# mini.net
KiCad netlist of a schematic drawn in Altium Designer
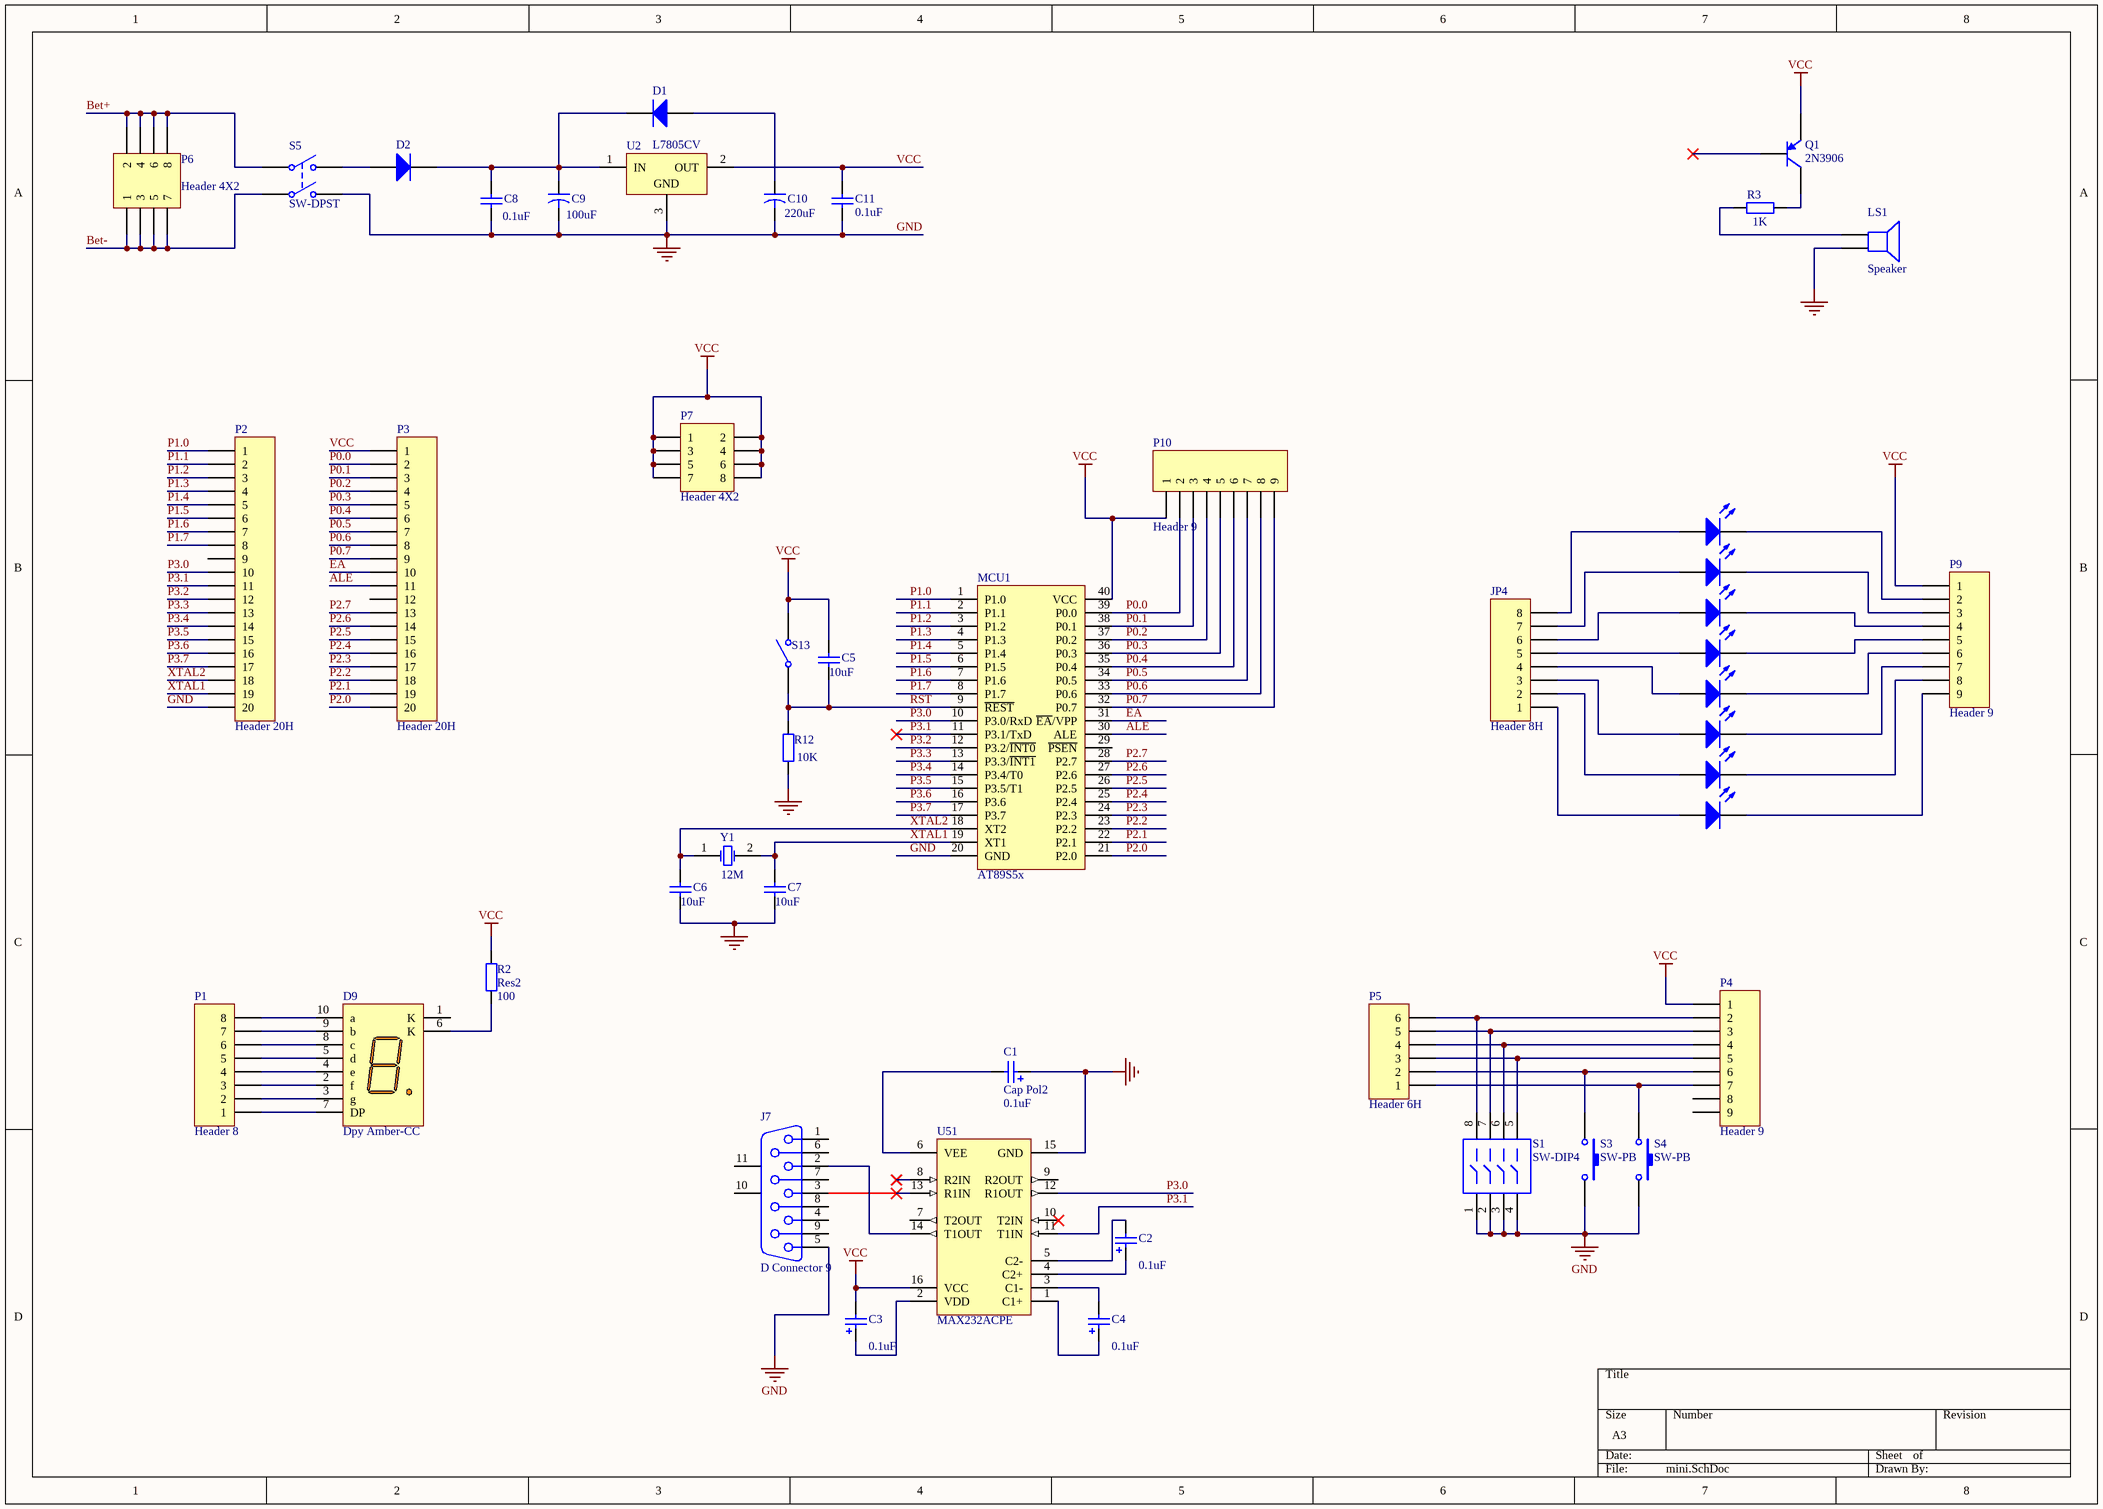
[diagram p0: mini.SchDoc]

(export (version "E")
  (design (tool "Eeschema 10.0.6"))
  (components
    (comp (ref "C1")
      (value "Cap Pol2")
      (footprint "POLAR0.8")
      (description "Polarized Capacitor (Axial)")
      (fields (field (name "ALTIUM_VALUE") "0.1uF") (field (name "PUBLISHER") "Altium Limited"))
      (libsource (lib "Miscellaneous Devices") (part "Cap Pol2"))
    )
    (comp (ref "C2")
      (value "0.1uF")
      (footprint "POLAR0.8")
      (description "Polarized Capacitor (Axial)")
      (fields (field (name "Comment") "Cap Pol2") (field (name "PUBLISHER") "Altium Limited"))
      (libsource (lib "Miscellaneous Devices") (part "Cap Pol2"))
    )
    (comp (ref "C3")
      (value "0.1uF")
      (footprint "POLAR0.8")
      (description "Polarized Capacitor (Axial)")
      (fields (field (name "Comment") "Cap Pol2") (field (name "PUBLISHER") "Altium Limited"))
      (libsource (lib "Miscellaneous Devices") (part "Cap Pol2"))
    )
    (comp (ref "C4")
      (value "0.1uF")
      (footprint "POLAR0.8")
      (description "Polarized Capacitor (Axial)")
      (fields (field (name "Comment") "Cap Pol2") (field (name "PUBLISHER") "Altium Limited"))
      (libsource (lib "Miscellaneous Devices") (part "Cap Pol2"))
    )
    (comp (ref "C5")
      (value "10uF")
      (footprint "CC 2.2*5")
      (description "Capacitor")
      (fields (field (name "Comment") "Cap") (field (name "PUBLISHER") "Altium Limited"))
      (libsource (lib "Miscellaneous Devices") (part "Cap"))
    )
    (comp (ref "C6")
      (value "10uF")
      (footprint "RAD-0.3")
      (description "Capacitor")
      (fields (field (name "Comment") "Cap") (field (name "PUBLISHER") "Altium Limited"))
      (libsource (lib "Miscellaneous Devices") (part "Cap"))
    )
    (comp (ref "C7")
      (value "10uF")
      (footprint "RAD-0.3")
      (description "Capacitor")
      (fields (field (name "Comment") "Cap") (field (name "PUBLISHER") "Altium Limited"))
      (libsource (lib "Miscellaneous Devices") (part "Cap"))
    )
    (comp (ref "C8")
      (value "0.1uF")
      (footprint "RAD-0.3")
      (description "Capacitor")
      (fields (field (name "Comment") "Cap") (field (name "PUBLISHER") "Altium Limited"))
      (libsource (lib "Miscellaneous Devices") (part "Cap"))
    )
    (comp (ref "C9")
      (value "100uF")
      (footprint "CAPR5-4X5")
      (description "Capacitor")
      (fields (field (name "Comment") "Cap2") (field (name "PUBLISHER") "Altium Limited"))
      (libsource (lib "Miscellaneous Devices") (part "Cap2"))
    )
    (comp (ref "C10")
      (value "220uF")
      (footprint "CAPR5-4X5")
      (description "Capacitor")
      (fields (field (name "Comment") "Cap2") (field (name "PUBLISHER") "Altium Limited"))
      (libsource (lib "Miscellaneous Devices") (part "Cap2"))
    )
    (comp (ref "C11")
      (value "0.1uF")
      (footprint "RAD-0.3")
      (description "Capacitor")
      (fields (field (name "Comment") "Cap") (field (name "PUBLISHER") "Altium Limited"))
      (libsource (lib "Miscellaneous Devices") (part "Cap"))
    )
    (comp (ref "D1")
      (value "Diode 1N4007")
      (footprint "DIODE-0.4")
      (description "1 Amp General Purpose Rectifier")
      (fields (field (name "PUBLISHER") "Altium Limited"))
      (libsource (lib "Miscellaneous Devices") (part "Diode 1N4007"))
    )
    (comp (ref "D2")
      (value "Diode 1N4148")
      (footprint "DIODE-0.4")
      (description "High Conductance Fast Diode")
      (fields (field (name "PUBLISHER") "Altium Limited"))
      (libsource (lib "Miscellaneous Devices") (part "Diode 1N4148"))
    )
    (comp (ref "D9")
      (value "Dpy Amber-CC")
      (footprint "H")
      (description "7.6 mm Black Surface 7-Segment Display: CC, RH DP")
      (fields (field (name "PUBLISHER") "Altium Limited"))
      (libsource (lib "Miscellaneous Devices") (part "Dpy Amber-CC"))
    )
    (comp (ref "DS11")
      (value "LED0")
      (footprint "PIN2")
      (description "Typical INFRARED GaAs LED")
      (fields (field (name "PUBLISHER") "Altium Limited"))
      (libsource (lib "Miscellaneous Devices") (part "LED0"))
    )
    (comp (ref "DS12")
      (value "LED0")
      (footprint "PIN2")
      (description "Typical INFRARED GaAs LED")
      (fields (field (name "PUBLISHER") "Altium Limited"))
      (libsource (lib "Miscellaneous Devices") (part "LED0"))
    )
    (comp (ref "DS13")
      (value "LED0")
      (footprint "PIN2")
      (description "Typical INFRARED GaAs LED")
      (fields (field (name "PUBLISHER") "Altium Limited"))
      (libsource (lib "Miscellaneous Devices") (part "LED0"))
    )
    (comp (ref "DS14")
      (value "LED0")
      (footprint "PIN2")
      (description "Typical INFRARED GaAs LED")
      (fields (field (name "PUBLISHER") "Altium Limited"))
      (libsource (lib "Miscellaneous Devices") (part "LED0"))
    )
    (comp (ref "DS15")
      (value "LED0")
      (footprint "PIN2")
      (description "Typical INFRARED GaAs LED")
      (fields (field (name "PUBLISHER") "Altium Limited"))
      (libsource (lib "Miscellaneous Devices") (part "LED0"))
    )
    (comp (ref "DS16")
      (value "LED0")
      (footprint "PIN2")
      (description "Typical INFRARED GaAs LED")
      (fields (field (name "PUBLISHER") "Altium Limited"))
      (libsource (lib "Miscellaneous Devices") (part "LED0"))
    )
    (comp (ref "DS17")
      (value "LED0")
      (footprint "PIN2")
      (description "Typical INFRARED GaAs LED")
      (fields (field (name "PUBLISHER") "Altium Limited"))
      (libsource (lib "Miscellaneous Devices") (part "LED0"))
    )
    (comp (ref "DS18")
      (value "LED0")
      (footprint "PIN2")
      (description "Typical INFRARED GaAs LED")
      (fields (field (name "PUBLISHER") "Altium Limited"))
      (libsource (lib "Miscellaneous Devices") (part "LED0"))
    )
    (comp (ref "J7")
      (value "D Connector 9")
      (footprint "DSUB1.385-2H9")
      (description "Receptacle Assembly, 9 Position, Right Angle")
      (fields (field (name "PUBLISHER") "Altium Limited"))
      (libsource (lib "Miscellaneous Connectors") (part "D Connector 9"))
    )
    (comp (ref "JP4")
      (value "Header 8H")
      (footprint "HDR1X8H")
      (description "Header, 8-Pin, Right Angle")
      (fields (field (name "PUBLISHER") "Altium Limited"))
      (libsource (lib "Miscellaneous Connectors") (part "Header 8H"))
    )
    (comp (ref "LS1")
      (value "Speaker")
      (footprint "BEEP 7.6X12X7.5")
      (description "Loudspeaker")
      (fields (field (name "PUBLISHER") "Altium Limited"))
      (libsource (lib "Miscellaneous Devices") (part "Speaker"))
    )
    (comp (ref "MCU1")
      (value "AT89S5x")
      (footprint "DIP40")
      (description "51单片机")
      (libsource (lib "单片机") (part "AT89S5x"))
    )
    (comp (ref "P1")
      (value "Header 8")
      (footprint "HDR1X8")
      (description "Header, 8-Pin")
      (fields (field (name "PUBLISHER") "Altium Limited"))
      (libsource (lib "Miscellaneous Connectors") (part "Header 8"))
    )
    (comp (ref "P2")
      (value "Header 20H")
      (footprint "HDR1X20")
      (description "Header, 20-Pin, Right Angle")
      (fields (field (name "PUBLISHER") "Altium Limited"))
      (libsource (lib "Miscellaneous Connectors") (part "Header 20H"))
    )
    (comp (ref "P3")
      (value "Header 20H")
      (footprint "HDR1X20")
      (description "Header, 20-Pin, Right Angle")
      (fields (field (name "PUBLISHER") "Altium Limited"))
      (libsource (lib "Miscellaneous Connectors") (part "Header 20H"))
    )
    (comp (ref "P4")
      (value "Header 9")
      (footprint "HDR1X9")
      (description "Header, 9-Pin")
      (fields (field (name "PUBLISHER") "Altium Limited"))
      (libsource (lib "Miscellaneous Connectors") (part "Header 9"))
    )
    (comp (ref "P5")
      (value "Header 6H")
      (footprint "HDR1X6H")
      (description "Header, 6-Pin, Right Angle")
      (fields (field (name "PUBLISHER") "Altium Limited"))
      (libsource (lib "Miscellaneous Connectors") (part "Header 6H"))
    )
    (comp (ref "P6")
      (value "Header 4X2")
      (footprint "HDR2X4")
      (description "Header, 4-Pin, Dual row")
      (fields (field (name "PUBLISHER") "Altium Limited"))
      (libsource (lib "Miscellaneous Connectors") (part "Header 4X2"))
    )
    (comp (ref "P7")
      (value "Header 4X2")
      (footprint "HDR2X4")
      (description "Header, 4-Pin, Dual row")
      (fields (field (name "PUBLISHER") "Altium Limited"))
      (libsource (lib "PCB_Project") (part "Header 4X2"))
    )
    (comp (ref "P9")
      (value "Header 9")
      (footprint "HDR1X9")
      (description "Header, 9-Pin")
      (fields (field (name "PUBLISHER") "Altium Limited"))
      (libsource (lib "PCB_Project") (part "Header 9"))
    )
    (comp (ref "P10")
      (value "Header 9")
      (footprint "HDR1X9")
      (description "Header, 9-Pin")
      (fields (field (name "PUBLISHER") "Altium Limited"))
      (libsource (lib "") (part "Header 9_1"))
    )
    (comp (ref "Q1")
      (value "2N3906")
      (footprint "BCY-W3/E4")
      (description "PNP General Purpose Amplifier")
      (fields (field (name "PUBLISHER") "Altium Limited"))
      (libsource (lib "Miscellaneous Devices") (part "2N3906"))
    )
    (comp (ref "R2")
      (value "Res2")
      (footprint "AXIAL-0.4")
      (description "Resistor")
      (fields (field (name "ALTIUM_VALUE") "100") (field (name "PUBLISHER") "Altium Limited"))
      (libsource (lib "") (part "Res2_1"))
    )
    (comp (ref "R3")
      (value "1K")
      (footprint "AXIAL-0.4")
      (description "Resistor")
      (fields (field (name "Comment") "Res2") (field (name "PUBLISHER") "Altium Limited"))
      (libsource (lib "Miscellaneous Devices") (part "Res2"))
    )
    (comp (ref "R12")
      (value "10K")
      (footprint "AXIAL-0.4")
      (description "Resistor")
      (fields (field (name "Comment") "Res2") (field (name "PUBLISHER") "Altium Limited"))
      (libsource (lib "") (part "Res2_2"))
    )
    (comp (ref "S1")
      (value "SW-DIP4")
      (footprint "Miscellaneous Devices:DIP-8")
      (description "DIP Switch")
      (fields (field (name "PUBLISHER") "Altium Limited"))
      (libsource (lib "Miscellaneous Devices") (part "SW-DIP4"))
    )
    (comp (ref "S3")
      (value "SW-PB")
      (footprint "SPST-2")
      (description "Switch")
      (fields (field (name "PUBLISHER") "Altium Limited"))
      (libsource (lib "Miscellaneous Devices") (part "SW-PB"))
    )
    (comp (ref "S4")
      (value "SW-PB")
      (footprint "SPST-2")
      (description "Switch")
      (fields (field (name "PUBLISHER") "Altium Limited"))
      (libsource (lib "Miscellaneous Devices") (part "SW-PB"))
    )
    (comp (ref "S5")
      (value "SW-DPST")
      (footprint "DPST-4")
      (description "Double-Pole, Single-Throw Switch")
      (fields (field (name "PUBLISHER") "Altium Limited"))
      (libsource (lib "Miscellaneous Devices") (part "SW-DPST"))
    )
    (comp (ref "S13")
      (value "SW-SPST")
      (footprint "SPST-2")
      (description "Single-Pole, Single-Throw Switch")
      (fields (field (name "PUBLISHER") "Altium Limited"))
      (libsource (lib "Miscellaneous Devices") (part "SW-SPST"))
    )
    (comp (ref "U2")
      (value "L7805CV")
      (footprint "D2PAK_N")
      (description "Positive Voltage Regulator")
      (fields (field (name "PUBLISHER") "Altium Limited"))
      (libsource (lib "ST Power Mgt Voltage Regulator") (part "L7805CV"))
    )
    (comp (ref "U51")
      (value "MAX232ACPE")
      (footprint "DIP-16")
      (description "+5V Powered, Multi-Channel RS-232 Driver/Receiver")
      (fields (field (name "PUBLISHER") "Altium Limited"))
      (libsource (lib "Maxim Communication Transceiver") (part "MAX232ACPE"))
    )
    (comp (ref "Y1")
      (value "12M")
      (footprint "BEEP 7.6X12X7.5")
      (description "Crystal Oscillator")
      (fields (field (name "Comment") "XTAL") (field (name "PUBLISHER") "Altium Limited"))
      (libsource (lib "Miscellaneous Devices") (part "XTAL"))
    )
  )
  (nets
    (net (code "2") (name "/ALE") (class "Default")
      (node (ref "MCU1") (pin "30") (pinfunction "ALE_30") (pintype "passive"))
      (node (ref "P3") (pin "11") (pinfunction "11_11") (pintype "passive"))
    )
    (net (code "3") (name "/Bet+") (class "Default")
      (node (ref "P6") (pin "2") (pinfunction "2_2") (pintype "passive"))
      (node (ref "P6") (pin "4") (pinfunction "4_4") (pintype "passive"))
      (node (ref "P6") (pin "6") (pinfunction "6_6") (pintype "passive"))
      (node (ref "P6") (pin "8") (pinfunction "8_8") (pintype "passive"))
      (node (ref "S5") (pin "1") (pinfunction "COMMON1_1") (pintype "passive"))
    )
    (net (code "4") (name "/Bet-") (class "Default")
      (node (ref "P6") (pin "1") (pinfunction "1_1") (pintype "passive"))
      (node (ref "P6") (pin "3") (pinfunction "3_3") (pintype "passive"))
      (node (ref "P6") (pin "5") (pinfunction "5_5") (pintype "passive"))
      (node (ref "P6") (pin "7") (pinfunction "7_7") (pintype "passive"))
      (node (ref "S5") (pin "3") (pinfunction "COMMON2_3") (pintype "passive"))
    )
    (net (code "5") (name "/P0.0") (class "Default")
      (node (ref "MCU1") (pin "39") (pinfunction "P0.0_39") (pintype "passive"))
      (node (ref "P10") (pin "2") (pinfunction "2_2") (pintype "passive"))
      (node (ref "P3") (pin "2") (pinfunction "2_2") (pintype "passive"))
    )
    (net (code "6") (name "/P0.1") (class "Default")
      (node (ref "MCU1") (pin "38") (pinfunction "P0.1_38") (pintype "passive"))
      (node (ref "P10") (pin "3") (pinfunction "3_3") (pintype "passive"))
      (node (ref "P3") (pin "3") (pinfunction "3_3") (pintype "passive"))
    )
    (net (code "7") (name "/P0.2") (class "Default")
      (node (ref "MCU1") (pin "37") (pinfunction "P0.2_37") (pintype "passive"))
      (node (ref "P10") (pin "4") (pinfunction "4_4") (pintype "passive"))
      (node (ref "P3") (pin "4") (pinfunction "4_4") (pintype "passive"))
    )
    (net (code "8") (name "/P0.3") (class "Default")
      (node (ref "MCU1") (pin "36") (pinfunction "P0.3_36") (pintype "passive"))
      (node (ref "P10") (pin "5") (pinfunction "5_5") (pintype "passive"))
      (node (ref "P3") (pin "5") (pinfunction "5_5") (pintype "passive"))
    )
    (net (code "9") (name "/P0.4") (class "Default")
      (node (ref "MCU1") (pin "35") (pinfunction "P0.4_35") (pintype "passive"))
      (node (ref "P10") (pin "6") (pinfunction "6_6") (pintype "passive"))
      (node (ref "P3") (pin "6") (pinfunction "6_6") (pintype "passive"))
    )
    (net (code "10") (name "/P0.5") (class "Default")
      (node (ref "MCU1") (pin "34") (pinfunction "P0.5_34") (pintype "passive"))
      (node (ref "P10") (pin "7") (pinfunction "7_7") (pintype "passive"))
      (node (ref "P3") (pin "7") (pinfunction "7_7") (pintype "passive"))
    )
    (net (code "11") (name "/P0.6") (class "Default")
      (node (ref "MCU1") (pin "33") (pinfunction "P0.6_33") (pintype "passive"))
      (node (ref "P10") (pin "8") (pinfunction "8_8") (pintype "passive"))
      (node (ref "P3") (pin "8") (pinfunction "8_8") (pintype "passive"))
    )
    (net (code "12") (name "/P0.7") (class "Default")
      (node (ref "MCU1") (pin "32") (pinfunction "P0.7_32") (pintype "passive"))
      (node (ref "P10") (pin "9") (pinfunction "9_9") (pintype "passive"))
      (node (ref "P3") (pin "9") (pinfunction "9_9") (pintype "passive"))
    )
    (net (code "13") (name "/P1.0") (class "Default")
      (node (ref "MCU1") (pin "1") (pinfunction "P1.0_1") (pintype "passive"))
      (node (ref "P2") (pin "1") (pinfunction "1_1") (pintype "passive"))
    )
    (net (code "14") (name "/P1.1") (class "Default")
      (node (ref "MCU1") (pin "2") (pinfunction "P1.1_2") (pintype "passive"))
      (node (ref "P2") (pin "2") (pinfunction "2_2") (pintype "passive"))
    )
    (net (code "15") (name "/P1.2") (class "Default")
      (node (ref "MCU1") (pin "3") (pinfunction "P1.2_3") (pintype "passive"))
      (node (ref "P2") (pin "3") (pinfunction "3_3") (pintype "passive"))
    )
    (net (code "16") (name "/P1.3") (class "Default")
      (node (ref "MCU1") (pin "4") (pinfunction "P1.3_4") (pintype "passive"))
      (node (ref "P2") (pin "4") (pinfunction "4_4") (pintype "passive"))
    )
    (net (code "17") (name "/P1.4") (class "Default")
      (node (ref "MCU1") (pin "5") (pinfunction "P1.4_5") (pintype "passive"))
      (node (ref "P2") (pin "5") (pinfunction "5_5") (pintype "passive"))
    )
    (net (code "18") (name "/P1.5") (class "Default")
      (node (ref "MCU1") (pin "6") (pinfunction "P1.5_6") (pintype "passive"))
      (node (ref "P2") (pin "6") (pinfunction "6_6") (pintype "passive"))
    )
    (net (code "19") (name "/P1.6") (class "Default")
      (node (ref "MCU1") (pin "7") (pinfunction "P1.6_7") (pintype "passive"))
      (node (ref "P2") (pin "7") (pinfunction "7_7") (pintype "passive"))
    )
    (net (code "20") (name "/P1.7") (class "Default")
      (node (ref "MCU1") (pin "8") (pinfunction "P1.7_8") (pintype "passive"))
      (node (ref "P2") (pin "8") (pinfunction "8_8") (pintype "passive"))
    )
    (net (code "21") (name "/P2.0") (class "Default")
      (node (ref "MCU1") (pin "21") (pinfunction "P2.0_21") (pintype "passive"))
      (node (ref "P3") (pin "20") (pinfunction "20_20") (pintype "passive"))
    )
    (net (code "22") (name "/P2.1") (class "Default")
      (node (ref "MCU1") (pin "22") (pinfunction "P2.1_22") (pintype "passive"))
      (node (ref "P3") (pin "19") (pinfunction "19_19") (pintype "passive"))
    )
    (net (code "23") (name "/P2.2") (class "Default")
      (node (ref "MCU1") (pin "23") (pinfunction "P2.2_23") (pintype "passive"))
      (node (ref "P3") (pin "18") (pinfunction "18_18") (pintype "passive"))
    )
    (net (code "24") (name "/P2.3") (class "Default")
      (node (ref "MCU1") (pin "24") (pinfunction "P2.3_24") (pintype "passive"))
      (node (ref "P3") (pin "17") (pinfunction "17_17") (pintype "passive"))
    )
    (net (code "25") (name "/P2.4") (class "Default")
      (node (ref "MCU1") (pin "25") (pinfunction "P2.4_25") (pintype "passive"))
      (node (ref "P3") (pin "16") (pinfunction "16_16") (pintype "passive"))
    )
    (net (code "26") (name "/P2.5") (class "Default")
      (node (ref "MCU1") (pin "26") (pinfunction "P2.5_26") (pintype "passive"))
      (node (ref "P3") (pin "15") (pinfunction "15_15") (pintype "passive"))
    )
    (net (code "27") (name "/P2.6") (class "Default")
      (node (ref "MCU1") (pin "27") (pinfunction "P2.6_27") (pintype "passive"))
      (node (ref "P3") (pin "14") (pinfunction "14_14") (pintype "passive"))
    )
    (net (code "28") (name "/P2.7") (class "Default")
      (node (ref "MCU1") (pin "28") (pinfunction "P2.7_28") (pintype "passive"))
      (node (ref "P3") (pin "13") (pinfunction "13_13") (pintype "passive"))
    )
    (net (code "29") (name "/P3.0") (class "Default")
      (node (ref "MCU1") (pin "10") (pinfunction "P3.0/RxD_10") (pintype "passive"))
      (node (ref "P2") (pin "10") (pinfunction "10_10") (pintype "passive"))
      (node (ref "U51") (pin "12") (pinfunction "R1OUT_12") (pintype "output"))
    )
    (net (code "30") (name "/P3.1") (class "Default")
      (node (ref "MCU1") (pin "11") (pinfunction "P3.1/TxD_11") (pintype "passive"))
      (node (ref "P2") (pin "11") (pinfunction "11_11") (pintype "passive"))
      (node (ref "U51") (pin "11") (pinfunction "T1IN_11") (pintype "input"))
    )
    (net (code "31") (name "/P3.2") (class "Default")
      (node (ref "MCU1") (pin "12") (pinfunction "P3.2/~{INT0}_12") (pintype "passive"))
      (node (ref "P2") (pin "12") (pinfunction "12_12") (pintype "passive"))
    )
    (net (code "32") (name "/P3.3") (class "Default")
      (node (ref "MCU1") (pin "13") (pinfunction "P3.3/~{INT1}_13") (pintype "passive"))
      (node (ref "P2") (pin "13") (pinfunction "13_13") (pintype "passive"))
    )
    (net (code "33") (name "/P3.4") (class "Default")
      (node (ref "MCU1") (pin "14") (pinfunction "P3.4/T0_14") (pintype "passive"))
      (node (ref "P2") (pin "14") (pinfunction "14_14") (pintype "passive"))
    )
    (net (code "34") (name "/P3.5") (class "Default")
      (node (ref "MCU1") (pin "15") (pinfunction "P3.5/T1_15") (pintype "passive"))
      (node (ref "P2") (pin "15") (pinfunction "15_15") (pintype "passive"))
    )
    (net (code "35") (name "/P3.6") (class "Default")
      (node (ref "MCU1") (pin "16") (pinfunction "P3.6_16") (pintype "passive"))
      (node (ref "P2") (pin "16") (pinfunction "16_16") (pintype "passive"))
    )
    (net (code "36") (name "/P3.7") (class "Default")
      (node (ref "MCU1") (pin "17") (pinfunction "P3.7_17") (pintype "passive"))
      (node (ref "P2") (pin "17") (pinfunction "17_17") (pintype "passive"))
    )
    (net (code "37") (name "/XTAL1") (class "Default")
      (node (ref "C7") (pin "2") (pinfunction "2_2") (pintype "passive"))
      (node (ref "MCU1") (pin "19") (pinfunction "XT1_19") (pintype "passive"))
      (node (ref "P2") (pin "19") (pinfunction "19_19") (pintype "passive"))
      (node (ref "Y1") (pin "2") (pinfunction "OSC2_2") (pintype "passive"))
    )
    (net (code "38") (name "/XTAL2") (class "Default")
      (node (ref "C6") (pin "2") (pinfunction "2_2") (pintype "passive"))
      (node (ref "MCU1") (pin "18") (pinfunction "XT2_18") (pintype "passive"))
      (node (ref "P2") (pin "18") (pinfunction "18_18") (pintype "passive"))
      (node (ref "Y1") (pin "1") (pinfunction "OSC1_1") (pintype "passive"))
    )
    (net (code "39") (name "/~{EA}") (class "Default")
      (node (ref "MCU1") (pin "31") (pinfunction "~{EA}/VPP_31") (pintype "passive"))
      (node (ref "P3") (pin "10") (pinfunction "10_10") (pintype "passive"))
    )
    (net (code "40") (name "/~{RST}") (class "Default")
      (node (ref "C5") (pin "1") (pinfunction "1_1") (pintype "passive"))
      (node (ref "MCU1") (pin "9") (pinfunction "~{REST}_9") (pintype "passive"))
      (node (ref "R12") (pin "2") (pinfunction "2_2") (pintype "passive"))
      (node (ref "S13") (pin "1") (pinfunction "COMMON_1") (pintype "passive"))
    )
    (net (code "41") (name "GND") (class "Default")
      (node (ref "C1") (pin "1") (pinfunction "1_1") (pintype "passive"))
      (node (ref "C10") (pin "2") (pinfunction "2_2") (pintype "passive"))
      (node (ref "C11") (pin "1") (pinfunction "1_1") (pintype "passive"))
      (node (ref "C6") (pin "1") (pinfunction "1_1") (pintype "passive"))
      (node (ref "C7") (pin "1") (pinfunction "1_1") (pintype "passive"))
      (node (ref "C8") (pin "1") (pinfunction "1_1") (pintype "passive"))
      (node (ref "C9") (pin "2") (pinfunction "2_2") (pintype "passive"))
      (node (ref "J7") (pin "5") (pinfunction "5_5") (pintype "passive"))
      (node (ref "LS1") (pin "2") (pinfunction "2_2") (pintype "passive"))
      (node (ref "MCU1") (pin "20") (pinfunction "GND_20") (pintype "passive"))
      (node (ref "P2") (pin "20") (pinfunction "20_20") (pintype "passive"))
      (node (ref "R12") (pin "1") (pinfunction "1_1") (pintype "passive"))
      (node (ref "S1") (pin "1") (pinfunction "1_1") (pintype "passive"))
      (node (ref "S1") (pin "2") (pinfunction "2_2") (pintype "passive"))
      (node (ref "S1") (pin "3") (pinfunction "3_3") (pintype "passive"))
      (node (ref "S1") (pin "4") (pinfunction "4_4") (pintype "passive"))
      (node (ref "S3") (pin "2") (pinfunction "2_2") (pintype "passive"))
      (node (ref "S4") (pin "2") (pinfunction "2_2") (pintype "passive"))
      (node (ref "S5") (pin "4") (pinfunction "NO2_4") (pintype "passive"))
      (node (ref "U2") (pin "3") (pinfunction "GND_3") (pintype "power_in"))
      (node (ref "U51") (pin "15") (pinfunction "GND_15") (pintype "power_in"))
    )
    (net (code "42") (name "Net-(D1-A)") (class "Default")
      (node (ref "C10") (pin "1") (pinfunction "1_1") (pintype "passive"))
      (node (ref "D1") (pin "1") (pinfunction "A_1") (pintype "passive"))
    )
    (net (code "43") (name "Net-(D1-K)") (class "Default")
      (node (ref "C8") (pin "2") (pinfunction "2_2") (pintype "passive"))
      (node (ref "C9") (pin "1") (pinfunction "1_1") (pintype "passive"))
      (node (ref "D1") (pin "2") (pinfunction "K_2") (pintype "passive"))
      (node (ref "D2") (pin "2") (pinfunction "K_2") (pintype "passive"))
      (node (ref "U2") (pin "1") (pinfunction "IN_1") (pintype "power_in"))
    )
    (net (code "44") (name "Net-(D2-A)") (class "Default")
      (node (ref "D2") (pin "1") (pinfunction "A_1") (pintype "passive"))
      (node (ref "S5") (pin "2") (pinfunction "NO1_2") (pintype "passive"))
    )
    (net (code "45") (name "Net-(D9-DP)") (class "Default")
      (node (ref "D9") (pin "7") (pinfunction "DP_7") (pintype "passive"))
      (node (ref "P1") (pin "1") (pinfunction "1_1") (pintype "passive"))
    )
    (net (code "46") (name "Net-(D9-K-Pad6)") (class "Default")
      (node (ref "D9") (pin "6") (pinfunction "K_6") (pintype "passive"))
      (node (ref "R2") (pin "2") (pinfunction "2_2") (pintype "passive"))
    )
    (net (code "47") (name "Net-(D9-a)") (class "Default")
      (node (ref "D9") (pin "10") (pinfunction "a_10") (pintype "passive"))
      (node (ref "P1") (pin "8") (pinfunction "8_8") (pintype "passive"))
    )
    (net (code "48") (name "Net-(D9-b)") (class "Default")
      (node (ref "D9") (pin "9") (pinfunction "b_9") (pintype "passive"))
      (node (ref "P1") (pin "7") (pinfunction "7_7") (pintype "passive"))
    )
    (net (code "49") (name "Net-(D9-c)") (class "Default")
      (node (ref "D9") (pin "8") (pinfunction "c_8") (pintype "passive"))
      (node (ref "P1") (pin "6") (pinfunction "6_6") (pintype "passive"))
    )
    (net (code "50") (name "Net-(D9-d)") (class "Default")
      (node (ref "D9") (pin "5") (pinfunction "d_5") (pintype "passive"))
      (node (ref "P1") (pin "5") (pinfunction "5_5") (pintype "passive"))
    )
    (net (code "51") (name "Net-(D9-e)") (class "Default")
      (node (ref "D9") (pin "4") (pinfunction "e_4") (pintype "passive"))
      (node (ref "P1") (pin "4") (pinfunction "4_4") (pintype "passive"))
    )
    (net (code "52") (name "Net-(D9-f)") (class "Default")
      (node (ref "D9") (pin "2") (pinfunction "f_2") (pintype "passive"))
      (node (ref "P1") (pin "3") (pinfunction "3_3") (pintype "passive"))
    )
    (net (code "53") (name "Net-(D9-g)") (class "Default")
      (node (ref "D9") (pin "3") (pinfunction "g_3") (pintype "passive"))
      (node (ref "P1") (pin "2") (pinfunction "2_2") (pintype "passive"))
    )
    (net (code "54") (name "Net-(DS11-A)") (class "Default")
      (node (ref "DS11") (pin "1") (pinfunction "A_1") (pintype "passive"))
      (node (ref "JP4") (pin "8") (pinfunction "8_8") (pintype "passive"))
    )
    (net (code "55") (name "Net-(DS11-K)") (class "Default")
      (node (ref "DS11") (pin "2") (pinfunction "K_2") (pintype "passive"))
      (node (ref "P9") (pin "2") (pinfunction "2_2") (pintype "passive"))
    )
    (net (code "56") (name "Net-(DS12-A)") (class "Default")
      (node (ref "DS12") (pin "1") (pinfunction "A_1") (pintype "passive"))
      (node (ref "JP4") (pin "7") (pinfunction "7_7") (pintype "passive"))
    )
    (net (code "57") (name "Net-(DS12-K)") (class "Default")
      (node (ref "DS12") (pin "2") (pinfunction "K_2") (pintype "passive"))
      (node (ref "P9") (pin "3") (pinfunction "3_3") (pintype "passive"))
    )
    (net (code "58") (name "Net-(DS13-A)") (class "Default")
      (node (ref "DS13") (pin "1") (pinfunction "A_1") (pintype "passive"))
      (node (ref "JP4") (pin "6") (pinfunction "6_6") (pintype "passive"))
    )
    (net (code "59") (name "Net-(DS13-K)") (class "Default")
      (node (ref "DS13") (pin "2") (pinfunction "K_2") (pintype "passive"))
      (node (ref "P9") (pin "4") (pinfunction "4_4") (pintype "passive"))
    )
    (net (code "60") (name "Net-(DS14-A)") (class "Default")
      (node (ref "DS14") (pin "1") (pinfunction "A_1") (pintype "passive"))
      (node (ref "JP4") (pin "5") (pinfunction "5_5") (pintype "passive"))
    )
    (net (code "61") (name "Net-(DS14-K)") (class "Default")
      (node (ref "DS14") (pin "2") (pinfunction "K_2") (pintype "passive"))
      (node (ref "P9") (pin "5") (pinfunction "5_5") (pintype "passive"))
    )
    (net (code "62") (name "Net-(DS15-A)") (class "Default")
      (node (ref "DS15") (pin "1") (pinfunction "A_1") (pintype "passive"))
      (node (ref "JP4") (pin "4") (pinfunction "4_4") (pintype "passive"))
    )
    (net (code "63") (name "Net-(DS15-K)") (class "Default")
      (node (ref "DS15") (pin "2") (pinfunction "K_2") (pintype "passive"))
      (node (ref "P9") (pin "6") (pinfunction "6_6") (pintype "passive"))
    )
    (net (code "64") (name "Net-(DS16-A)") (class "Default")
      (node (ref "DS16") (pin "1") (pinfunction "A_1") (pintype "passive"))
      (node (ref "JP4") (pin "3") (pinfunction "3_3") (pintype "passive"))
    )
    (net (code "65") (name "Net-(DS16-K)") (class "Default")
      (node (ref "DS16") (pin "2") (pinfunction "K_2") (pintype "passive"))
      (node (ref "P9") (pin "7") (pinfunction "7_7") (pintype "passive"))
    )
    (net (code "66") (name "Net-(DS17-A)") (class "Default")
      (node (ref "DS17") (pin "1") (pinfunction "A_1") (pintype "passive"))
      (node (ref "JP4") (pin "2") (pinfunction "2_2") (pintype "passive"))
    )
    (net (code "67") (name "Net-(DS17-K)") (class "Default")
      (node (ref "DS17") (pin "2") (pinfunction "K_2") (pintype "passive"))
      (node (ref "P9") (pin "8") (pinfunction "8_8") (pintype "passive"))
    )
    (net (code "68") (name "Net-(DS18-A)") (class "Default")
      (node (ref "DS18") (pin "1") (pinfunction "A_1") (pintype "passive"))
      (node (ref "JP4") (pin "1") (pinfunction "1_1") (pintype "passive"))
    )
    (net (code "69") (name "Net-(DS18-K)") (class "Default")
      (node (ref "DS18") (pin "2") (pinfunction "K_2") (pintype "passive"))
      (node (ref "P9") (pin "9") (pinfunction "9_9") (pintype "passive"))
    )
    (net (code "70") (name "Net-(LS1-Pad1)") (class "Default")
      (node (ref "LS1") (pin "1") (pinfunction "1_1") (pintype "passive"))
      (node (ref "R3") (pin "1") (pinfunction "1_1") (pintype "passive"))
    )
    (net (code "71") (name "Net-(P4-Pad2)") (class "Default")
      (node (ref "P4") (pin "2") (pinfunction "2_2") (pintype "passive"))
      (node (ref "P5") (pin "6") (pinfunction "6_6") (pintype "passive"))
      (node (ref "S1") (pin "8") (pinfunction "8_8") (pintype "passive"))
    )
    (net (code "72") (name "Net-(P4-Pad3)") (class "Default")
      (node (ref "P4") (pin "3") (pinfunction "3_3") (pintype "passive"))
      (node (ref "P5") (pin "5") (pinfunction "5_5") (pintype "passive"))
      (node (ref "S1") (pin "7") (pinfunction "7_7") (pintype "passive"))
    )
    (net (code "73") (name "Net-(P4-Pad4)") (class "Default")
      (node (ref "P4") (pin "4") (pinfunction "4_4") (pintype "passive"))
      (node (ref "P5") (pin "4") (pinfunction "4_4") (pintype "passive"))
      (node (ref "S1") (pin "6") (pinfunction "6_6") (pintype "passive"))
    )
    (net (code "74") (name "Net-(P4-Pad5)") (class "Default")
      (node (ref "P4") (pin "5") (pinfunction "5_5") (pintype "passive"))
      (node (ref "P5") (pin "3") (pinfunction "3_3") (pintype "passive"))
      (node (ref "S1") (pin "5") (pinfunction "5_5") (pintype "passive"))
    )
    (net (code "75") (name "Net-(P4-Pad6)") (class "Default")
      (node (ref "P4") (pin "6") (pinfunction "6_6") (pintype "passive"))
      (node (ref "P5") (pin "2") (pinfunction "2_2") (pintype "passive"))
      (node (ref "S3") (pin "1") (pinfunction "1_1") (pintype "passive"))
    )
    (net (code "76") (name "Net-(P4-Pad7)") (class "Default")
      (node (ref "P4") (pin "7") (pinfunction "7_7") (pintype "passive"))
      (node (ref "P5") (pin "1") (pinfunction "1_1") (pintype "passive"))
      (node (ref "S4") (pin "1") (pinfunction "1_1") (pintype "passive"))
    )
    (net (code "77") (name "Net-(Q1-C)") (class "Default")
      (node (ref "Q1") (pin "3") (pinfunction "C_3") (pintype "passive"))
      (node (ref "R3") (pin "2") (pinfunction "2_2") (pintype "passive"))
    )
    (net (code "78") (name "Net-(U51-C1+)") (class "Default")
      (node (ref "C4") (pin "1") (pinfunction "1_1") (pintype "passive"))
      (node (ref "U51") (pin "1") (pinfunction "C1+_1") (pintype "passive"))
    )
    (net (code "79") (name "Net-(U51-C1-)") (class "Default")
      (node (ref "C4") (pin "2") (pinfunction "2_2") (pintype "passive"))
      (node (ref "U51") (pin "3") (pinfunction "C1-_3") (pintype "passive"))
    )
    (net (code "80") (name "Net-(U51-C2+)") (class "Default")
      (node (ref "C2") (pin "1") (pinfunction "1_1") (pintype "passive"))
      (node (ref "U51") (pin "4") (pinfunction "C2+_4") (pintype "passive"))
    )
    (net (code "81") (name "Net-(U51-C2-)") (class "Default")
      (node (ref "C2") (pin "2") (pinfunction "2_2") (pintype "passive"))
      (node (ref "U51") (pin "5") (pinfunction "C2-_5") (pintype "passive"))
    )
    (net (code "82") (name "Net-(U51-T1OUT)") (class "Default")
      (node (ref "J7") (pin "2") (pinfunction "2_2") (pintype "passive"))
      (node (ref "U51") (pin "14") (pinfunction "T1OUT_14") (pintype "output"))
    )
    (net (code "83") (name "Net-(U51-VDD)") (class "Default")
      (node (ref "C3") (pin "1") (pinfunction "1_1") (pintype "passive"))
      (node (ref "U51") (pin "2") (pinfunction "VDD_2") (pintype "power_in"))
    )
    (net (code "84") (name "Net-(U51-VEE)") (class "Default")
      (node (ref "C1") (pin "2") (pinfunction "2_2") (pintype "passive"))
      (node (ref "U51") (pin "6") (pinfunction "VEE_6") (pintype "power_in"))
    )
    (net (code "85") (name "VCC") (class "Default")
      (node (ref "C11") (pin "2") (pinfunction "2_2") (pintype "passive"))
      (node (ref "C3") (pin "2") (pinfunction "2_2") (pintype "passive"))
      (node (ref "C5") (pin "2") (pinfunction "2_2") (pintype "passive"))
      (node (ref "MCU1") (pin "40") (pinfunction "VCC_40") (pintype "passive"))
      (node (ref "P10") (pin "1") (pinfunction "1_1") (pintype "passive"))
      (node (ref "P3") (pin "1") (pinfunction "1_1") (pintype "passive"))
      (node (ref "P4") (pin "1") (pinfunction "1_1") (pintype "passive"))
      (node (ref "P7") (pin "1") (pinfunction "1_1") (pintype "passive"))
      (node (ref "P7") (pin "2") (pinfunction "2_2") (pintype "passive"))
      (node (ref "P7") (pin "3") (pinfunction "3_3") (pintype "passive"))
      (node (ref "P7") (pin "4") (pinfunction "4_4") (pintype "passive"))
      (node (ref "P7") (pin "5") (pinfunction "5_5") (pintype "passive"))
      (node (ref "P7") (pin "6") (pinfunction "6_6") (pintype "passive"))
      (node (ref "P7") (pin "7") (pinfunction "7_7") (pintype "passive"))
      (node (ref "P7") (pin "8") (pinfunction "8_8") (pintype "passive"))
      (node (ref "P9") (pin "1") (pinfunction "1_1") (pintype "passive"))
      (node (ref "Q1") (pin "1") (pinfunction "E_1") (pintype "passive"))
      (node (ref "R2") (pin "1") (pinfunction "1_1") (pintype "passive"))
      (node (ref "S13") (pin "2") (pinfunction "NO_2") (pintype "passive"))
      (node (ref "U2") (pin "2") (pinfunction "OUT_2") (pintype "power_in"))
      (node (ref "U51") (pin "16") (pinfunction "VCC_16") (pintype "power_in"))
    )
    (net (code "86") (name "unconnected-(D9-K-Pad1)") (class "Default")
      (node (ref "D9") (pin "1") (pinfunction "K_1") (pintype "passive"))
    )
    (net (code "87") (name "unconnected-(J7-MH1-Pad10)") (class "Default")
      (node (ref "J7") (pin "10") (pinfunction "MH1_10") (pintype "passive"))
    )
    (net (code "88") (name "unconnected-(J7-MH2-Pad11)") (class "Default")
      (node (ref "J7") (pin "11") (pinfunction "MH2_11") (pintype "passive"))
    )
    (net (code "89") (name "unconnected-(J7-Pad1)") (class "Default")
      (node (ref "J7") (pin "1") (pinfunction "1_1") (pintype "passive"))
    )
    (net (code "90") (name "unconnected-(J7-Pad3)") (class "Default")
      (node (ref "J7") (pin "3") (pinfunction "3_3") (pintype "passive"))
    )
    (net (code "91") (name "unconnected-(J7-Pad4)") (class "Default")
      (node (ref "J7") (pin "4") (pinfunction "4_4") (pintype "passive"))
    )
    (net (code "92") (name "unconnected-(J7-Pad6)") (class "Default")
      (node (ref "J7") (pin "6") (pinfunction "6_6") (pintype "passive"))
    )
    (net (code "93") (name "unconnected-(J7-Pad7)") (class "Default")
      (node (ref "J7") (pin "7") (pinfunction "7_7") (pintype "passive"))
    )
    (net (code "94") (name "unconnected-(J7-Pad8)") (class "Default")
      (node (ref "J7") (pin "8") (pinfunction "8_8") (pintype "passive"))
    )
    (net (code "95") (name "unconnected-(J7-Pad9)") (class "Default")
      (node (ref "J7") (pin "9") (pinfunction "9_9") (pintype "passive"))
    )
    (net (code "96") (name "unconnected-(MCU1-~{PSEN}-Pad29)") (class "Default")
      (node (ref "MCU1") (pin "29") (pinfunction "~{PSEN}_29") (pintype "passive"))
    )
    (net (code "97") (name "unconnected-(P2-Pad9)") (class "Default")
      (node (ref "P2") (pin "9") (pinfunction "9_9") (pintype "passive"))
    )
    (net (code "98") (name "unconnected-(P3-Pad12)") (class "Default")
      (node (ref "P3") (pin "12") (pinfunction "12_12") (pintype "passive"))
    )
    (net (code "99") (name "unconnected-(P4-Pad8)") (class "Default")
      (node (ref "P4") (pin "8") (pinfunction "8_8") (pintype "passive"))
    )
    (net (code "100") (name "unconnected-(P4-Pad9)") (class "Default")
      (node (ref "P4") (pin "9") (pinfunction "9_9") (pintype "passive"))
    )
    (net (code "101") (name "unconnected-(Q1-B-Pad2)") (class "Default")
      (node (ref "Q1") (pin "2") (pinfunction "B_2") (pintype "passive+no_connect"))
    )
    (net (code "102") (name "unconnected-(U51-R1IN-Pad13)") (class "Default")
      (node (ref "U51") (pin "13") (pinfunction "R1IN_13") (pintype "input+no_connect"))
    )
    (net (code "103") (name "unconnected-(U51-R2IN-Pad8)") (class "Default")
      (node (ref "U51") (pin "8") (pinfunction "R2IN_8") (pintype "input+no_connect"))
    )
    (net (code "104") (name "unconnected-(U51-R2OUT-Pad9)") (class "Default")
      (node (ref "U51") (pin "9") (pinfunction "R2OUT_9") (pintype "output"))
    )
    (net (code "105") (name "unconnected-(U51-T2IN-Pad10)") (class "Default")
      (node (ref "U51") (pin "10") (pinfunction "T2IN_10") (pintype "input+no_connect"))
    )
    (net (code "106") (name "unconnected-(U51-T2OUT-Pad7)") (class "Default")
      (node (ref "U51") (pin "7") (pinfunction "T2OUT_7") (pintype "output"))
    )
  )
)
